# schematic1.net
KiCad netlist of a schematic drawn in EAGLE
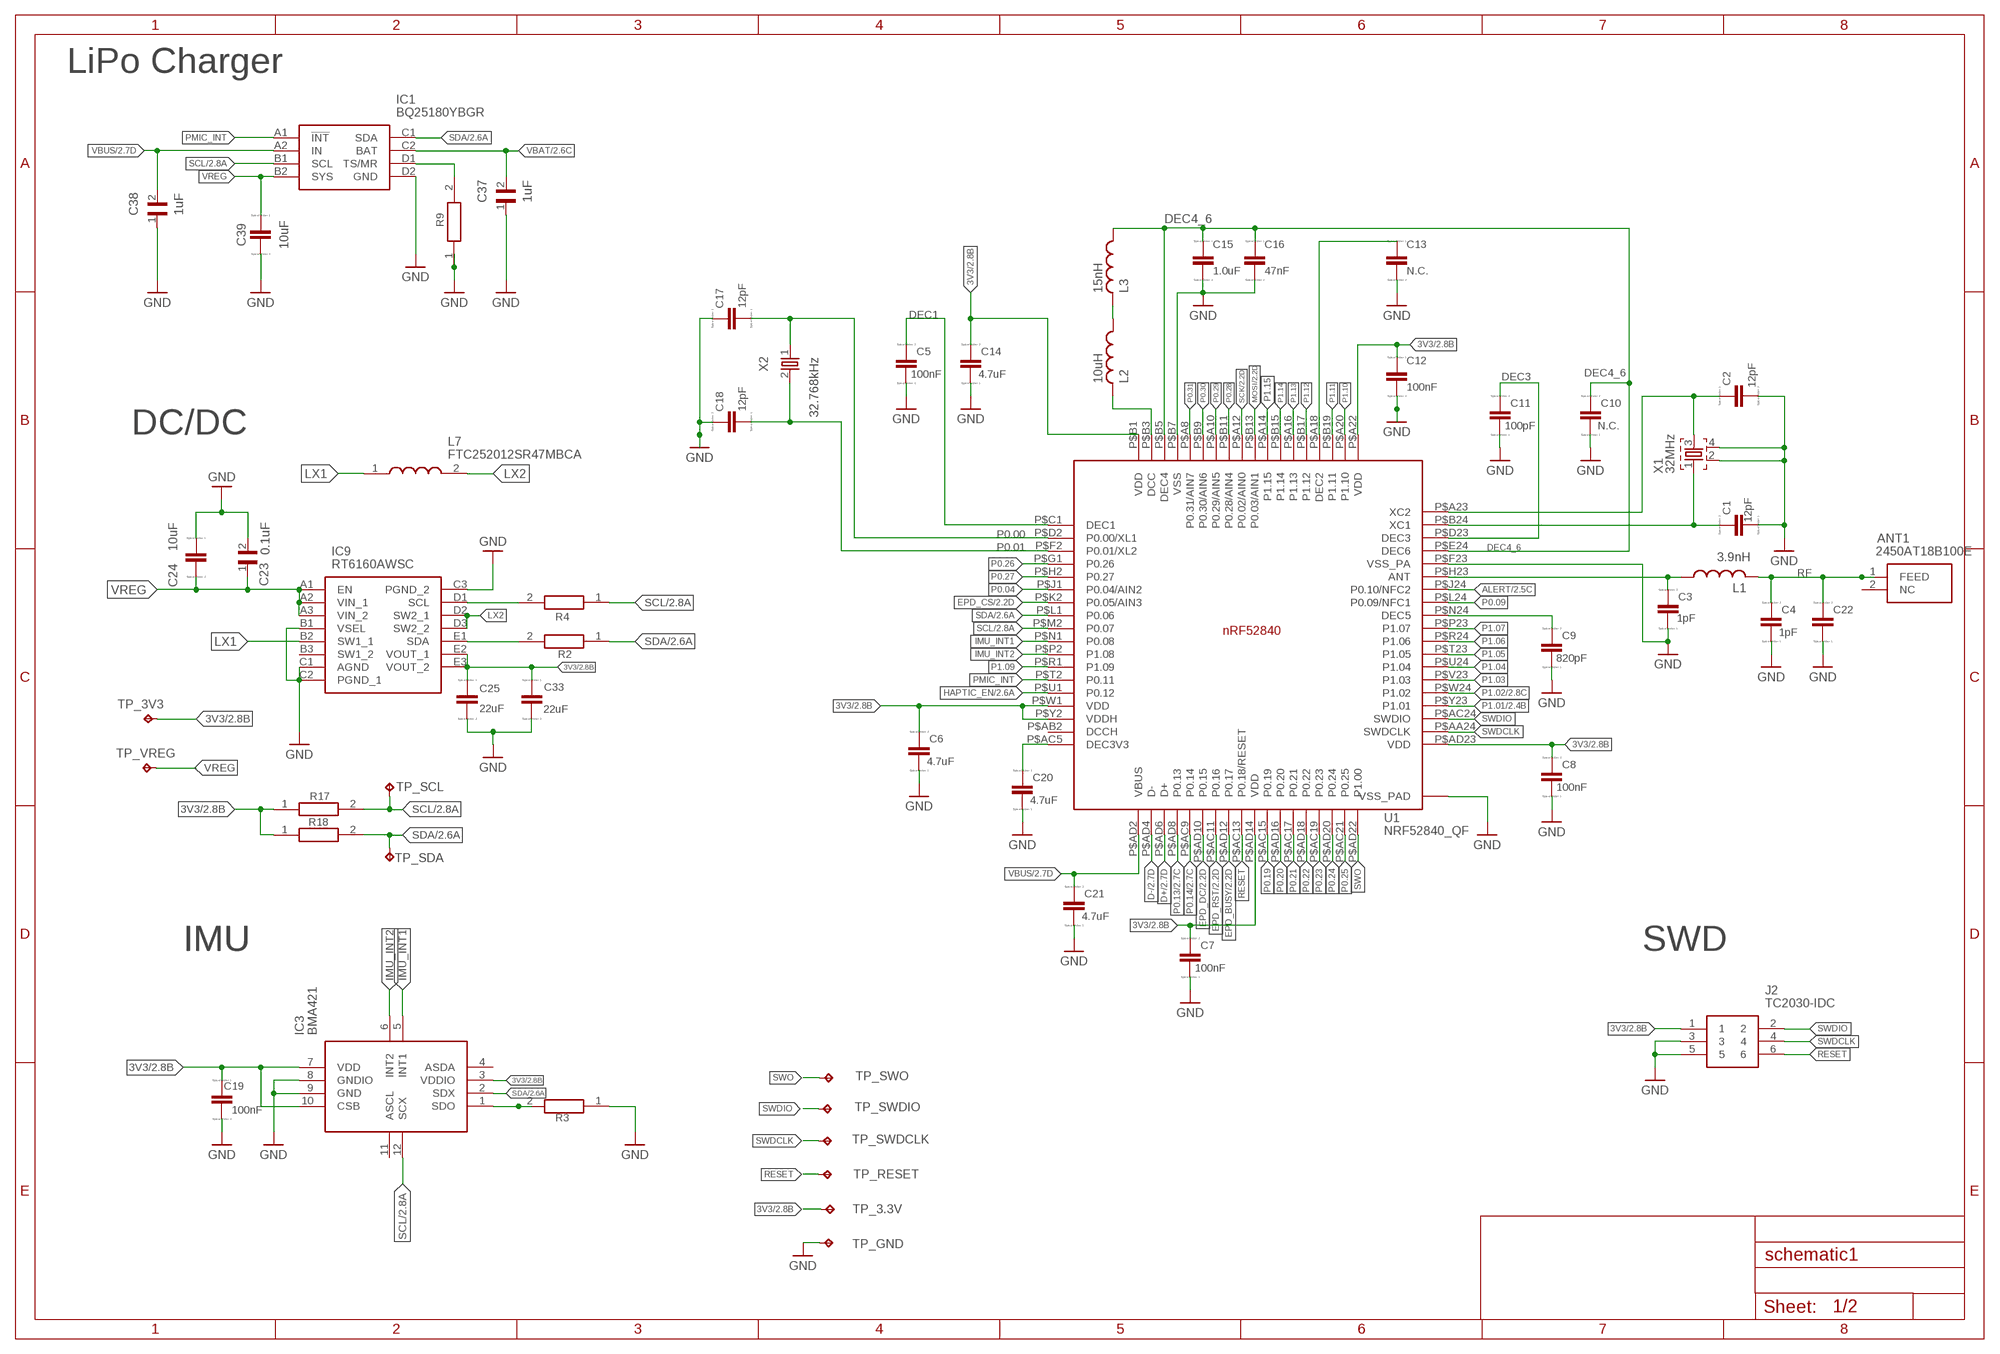
[diagram p0: schematic, sheet 1]
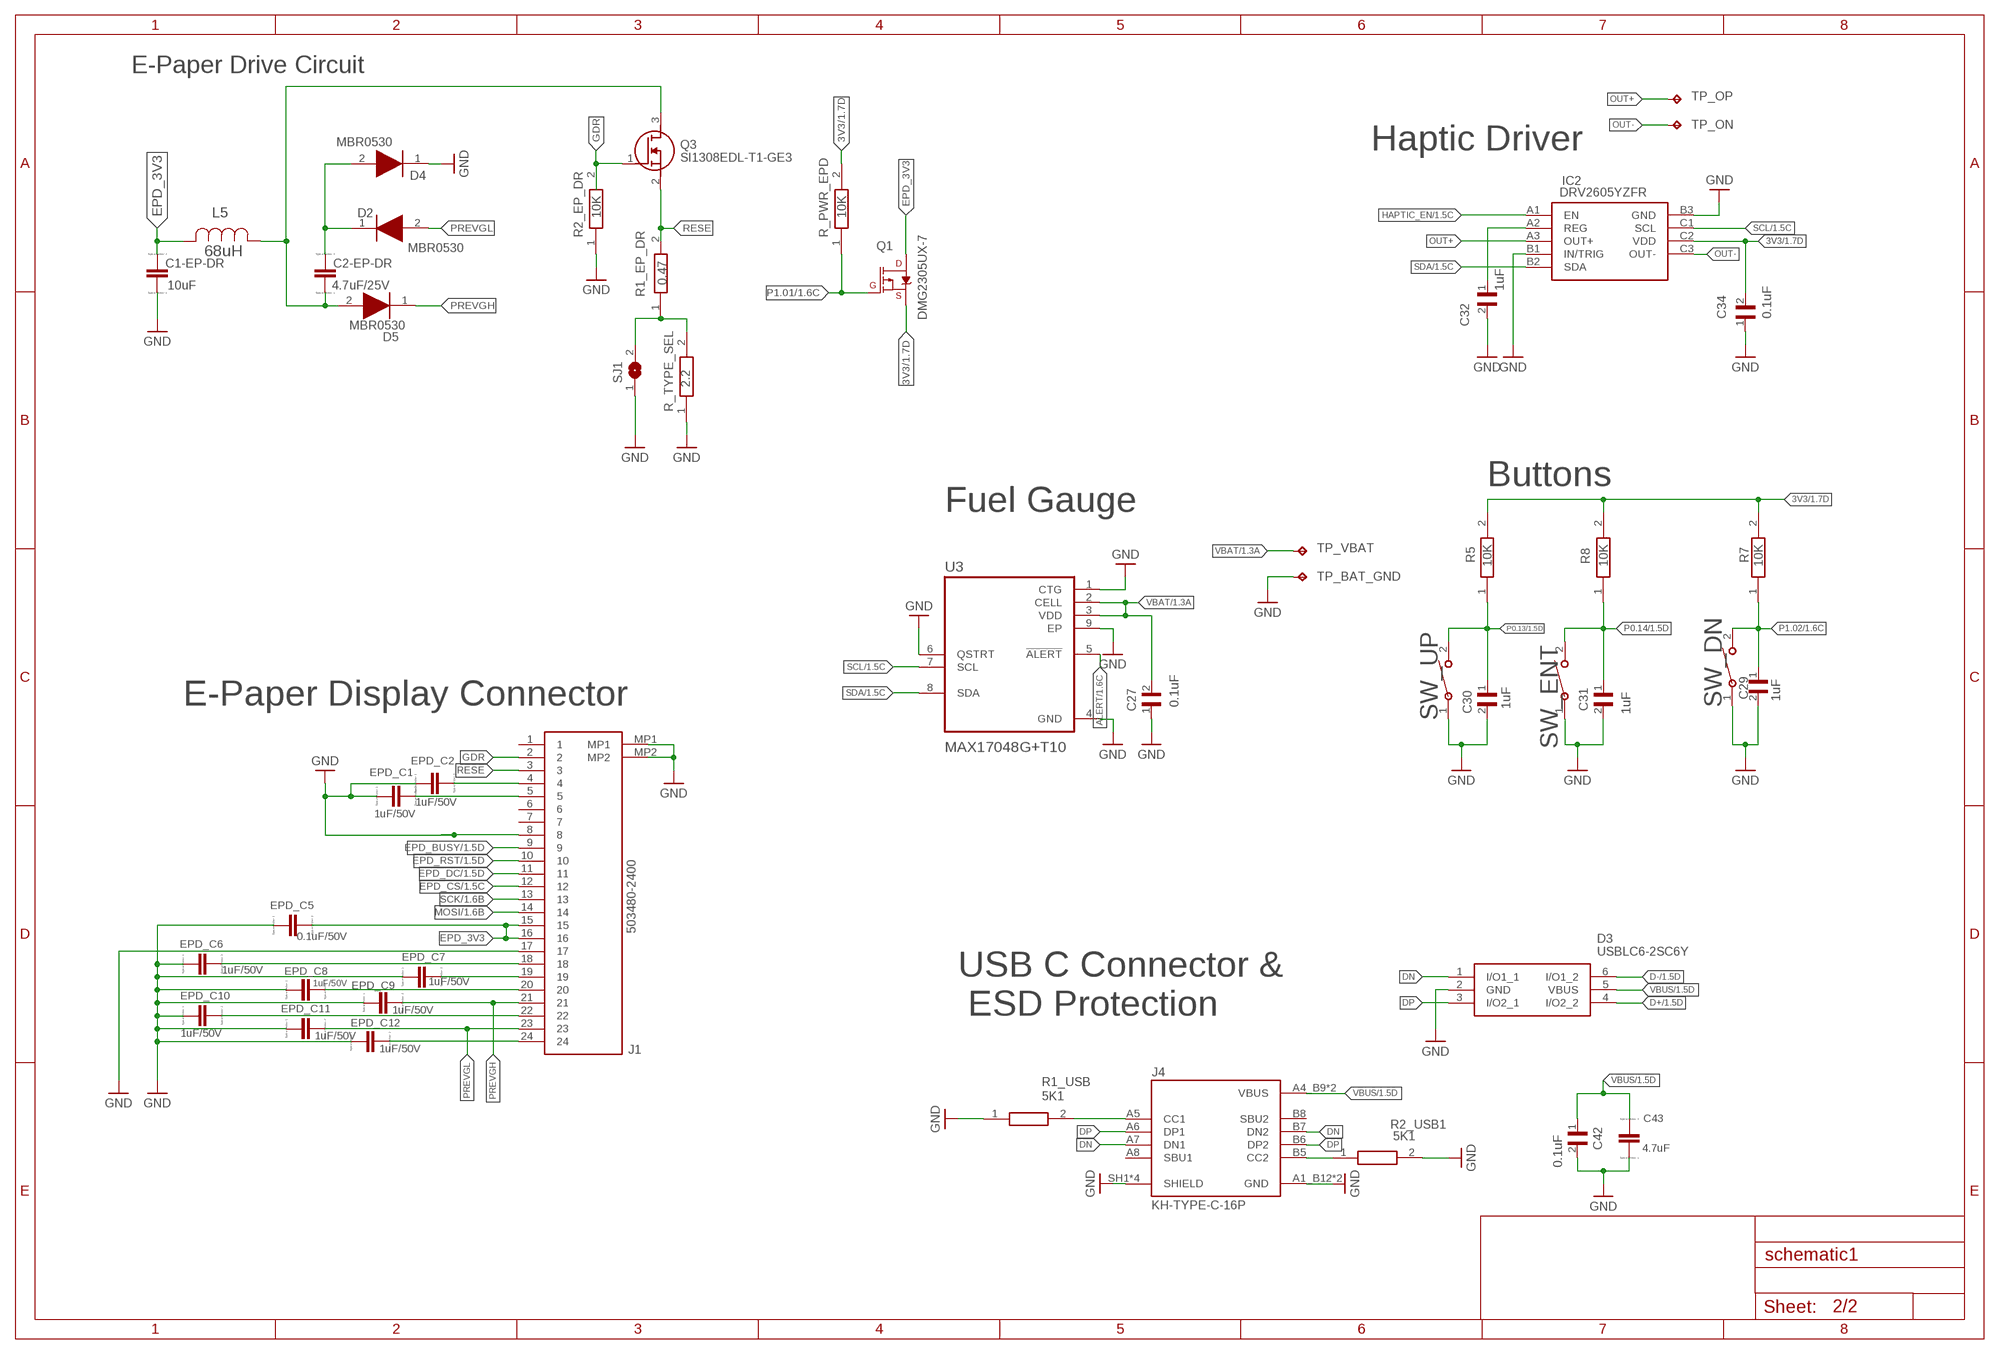
[diagram p1: schematic, sheet 2]

(export (version "E")
  (design (tool "Eeschema 10.0.6"))
  (components
    (comp (ref "ANT1")
      (value "2450AT18B100E")
      (footprint "eagle-import:2450AT18B100E_ANTC3216X140N")
      (fields (field (name "MOUSER_PART_NUMBER") "609-2450AT18B100E"))
      (libsource (lib "eagle-import") (part "2450AT18B100E_2450AT18B100E"))
    )
    (comp (ref "C1")
      (value "12pF")
      (footprint "eagle-import:ESP32_C6_LIBRARY_1_ESP32_WROVER_EAGLE-LTSPICE_C0402")
      (libsource (lib "eagle-import") (part "ESP32_C6_LIBRARY_1_ESP32_WROVER_EAGLE-LTSPICE_CC0402"))
    )
    (comp (ref "C2")
      (value "12pF")
      (footprint "eagle-import:ESP32_C6_LIBRARY_1_ESP32_WROVER_EAGLE-LTSPICE_C0402")
      (libsource (lib "eagle-import") (part "ESP32_C6_LIBRARY_1_ESP32_WROVER_EAGLE-LTSPICE_CC0402"))
    )
    (comp (ref "C3")
      (value "1pF")
      (footprint "eagle-import:ESP32_C6_LIBRARY_1_ESP32_WROVER_EAGLE-LTSPICE_C0402")
      (libsource (lib "eagle-import") (part "ESP32_C6_LIBRARY_1_ESP32_WROVER_EAGLE-LTSPICE_CC0402"))
    )
    (comp (ref "C4")
      (value "1pF")
      (footprint "eagle-import:ESP32_C6_LIBRARY_1_ESP32_WROVER_EAGLE-LTSPICE_C0402")
      (libsource (lib "eagle-import") (part "ESP32_C6_LIBRARY_1_ESP32_WROVER_EAGLE-LTSPICE_CC0402"))
    )
    (comp (ref "C5")
      (value "100nF")
      (footprint "eagle-import:ESP32_C6_LIBRARY_1_ESP32_WROVER_EAGLE-LTSPICE_C0402")
      (libsource (lib "eagle-import") (part "ESP32_C6_LIBRARY_1_ESP32_WROVER_EAGLE-LTSPICE_CC0402"))
    )
    (comp (ref "C6")
      (value "4.7uF")
      (footprint "eagle-import:ESP32_C6_LIBRARY_1_ESP32_WROVER_EAGLE-LTSPICE_C0402")
      (libsource (lib "eagle-import") (part "ESP32_C6_LIBRARY_1_ESP32_WROVER_EAGLE-LTSPICE_CC0402"))
    )
    (comp (ref "C7")
      (value "100nF")
      (footprint "eagle-import:ESP32_C6_LIBRARY_1_ESP32_WROVER_EAGLE-LTSPICE_C0402")
      (libsource (lib "eagle-import") (part "ESP32_C6_LIBRARY_1_ESP32_WROVER_EAGLE-LTSPICE_CC0402"))
    )
    (comp (ref "C8")
      (value "100nF")
      (footprint "eagle-import:ESP32_C6_LIBRARY_1_ESP32_WROVER_EAGLE-LTSPICE_C0402")
      (libsource (lib "eagle-import") (part "ESP32_C6_LIBRARY_1_ESP32_WROVER_EAGLE-LTSPICE_CC0402"))
    )
    (comp (ref "C9")
      (value "820pF")
      (footprint "eagle-import:ESP32_C6_LIBRARY_1_ESP32_WROVER_EAGLE-LTSPICE_C0402")
      (libsource (lib "eagle-import") (part "ESP32_C6_LIBRARY_1_ESP32_WROVER_EAGLE-LTSPICE_CC0402"))
    )
    (comp (ref "C10")
      (value "N.C.")
      (footprint "eagle-import:ESP32_C6_LIBRARY_1_ESP32_WROVER_EAGLE-LTSPICE_C0402")
      (libsource (lib "eagle-import") (part "ESP32_C6_LIBRARY_1_ESP32_WROVER_EAGLE-LTSPICE_CC0402"))
    )
    (comp (ref "C11")
      (value "100pF")
      (footprint "eagle-import:ESP32_C6_LIBRARY_1_ESP32_WROVER_EAGLE-LTSPICE_C0402")
      (libsource (lib "eagle-import") (part "ESP32_C6_LIBRARY_1_ESP32_WROVER_EAGLE-LTSPICE_CC0402"))
    )
    (comp (ref "C12")
      (value "100nF")
      (footprint "eagle-import:ESP32_C6_LIBRARY_1_ESP32_WROVER_EAGLE-LTSPICE_C0402")
      (libsource (lib "eagle-import") (part "ESP32_C6_LIBRARY_1_ESP32_WROVER_EAGLE-LTSPICE_CC0402"))
    )
    (comp (ref "C13")
      (value "N.C.")
      (footprint "eagle-import:ESP32_C6_LIBRARY_1_ESP32_WROVER_EAGLE-LTSPICE_C0402")
      (libsource (lib "eagle-import") (part "ESP32_C6_LIBRARY_1_ESP32_WROVER_EAGLE-LTSPICE_CC0402"))
    )
    (comp (ref "C14")
      (value "4.7uF")
      (footprint "eagle-import:ESP32_C6_LIBRARY_1_ESP32_WROVER_EAGLE-LTSPICE_C0402")
      (libsource (lib "eagle-import") (part "ESP32_C6_LIBRARY_1_ESP32_WROVER_EAGLE-LTSPICE_CC0402"))
    )
    (comp (ref "C15")
      (value "1.0uF")
      (footprint "eagle-import:ESP32_C6_LIBRARY_1_ESP32_WROVER_EAGLE-LTSPICE_C0402")
      (libsource (lib "eagle-import") (part "ESP32_C6_LIBRARY_1_ESP32_WROVER_EAGLE-LTSPICE_CC0402"))
    )
    (comp (ref "C16")
      (value "47nF")
      (footprint "eagle-import:ESP32_C6_LIBRARY_1_ESP32_WROVER_EAGLE-LTSPICE_C0402")
      (libsource (lib "eagle-import") (part "ESP32_C6_LIBRARY_1_ESP32_WROVER_EAGLE-LTSPICE_CC0402"))
    )
    (comp (ref "C17")
      (value "12pF")
      (footprint "eagle-import:ESP32_C6_LIBRARY_1_ESP32_WROVER_EAGLE-LTSPICE_C0402")
      (libsource (lib "eagle-import") (part "ESP32_C6_LIBRARY_1_ESP32_WROVER_EAGLE-LTSPICE_CC0402"))
    )
    (comp (ref "C18")
      (value "12pF")
      (footprint "eagle-import:ESP32_C6_LIBRARY_1_ESP32_WROVER_EAGLE-LTSPICE_C0402")
      (libsource (lib "eagle-import") (part "ESP32_C6_LIBRARY_1_ESP32_WROVER_EAGLE-LTSPICE_CC0402"))
    )
    (comp (ref "C19")
      (value "100nF")
      (footprint "eagle-import:ESP32_C6_LIBRARY_1_ESP32_WROVER_EAGLE-LTSPICE_C0402")
      (libsource (lib "eagle-import") (part "ESP32_C6_LIBRARY_1_ESP32_WROVER_EAGLE-LTSPICE_CC0402"))
    )
    (comp (ref "C20")
      (value "4.7uF")
      (footprint "eagle-import:ESP32_C6_LIBRARY_1_ESP32_WROVER_EAGLE-LTSPICE_C0402")
      (libsource (lib "eagle-import") (part "ESP32_C6_LIBRARY_1_ESP32_WROVER_EAGLE-LTSPICE_CC0402"))
    )
    (comp (ref "C21")
      (value "4.7uF")
      (footprint "eagle-import:ESP32_C6_LIBRARY_1_ESP32_WROVER_EAGLE-LTSPICE_C0402")
      (libsource (lib "eagle-import") (part "ESP32_C6_LIBRARY_1_ESP32_WROVER_EAGLE-LTSPICE_CC0402"))
    )
    (comp (ref "C22")
      (value "N.C.")
      (footprint "eagle-import:ESP32_C6_LIBRARY_1_ESP32_WROVER_EAGLE-LTSPICE_C0402")
      (libsource (lib "eagle-import") (part "ESP32_C6_LIBRARY_1_ESP32_WROVER_EAGLE-LTSPICE_CC0402"))
    )
    (comp (ref "C23")
      (value "0.1uF")
      (footprint "eagle-import:GRM011R60J152KE01L_2_CAPC0201X13N")
      (fields (field (name "MF") "Murata") (field (name "MP") "GRM011R60J152KE01L"))
      (libsource (lib "eagle-import") (part "GRM011R60J152KE01L_2_GRM011R60J152KE01L"))
    )
    (comp (ref "C24")
      (value "10uF")
      (footprint "eagle-import:ESP32_C6_LIBRARY_1_ESP32_WROVER_EAGLE-LTSPICE_C0402")
      (libsource (lib "eagle-import") (part "ESP32_C6_LIBRARY_1_ESP32_WROVER_EAGLE-LTSPICE_CC0402"))
    )
    (comp (ref "C25")
      (value "22uF")
      (footprint "eagle-import:ESP32_C6_LIBRARY_1_ESP32_WROVER_EAGLE-LTSPICE_C0402")
      (libsource (lib "eagle-import") (part "ESP32_C6_LIBRARY_1_ESP32_WROVER_EAGLE-LTSPICE_CC0402"))
    )
    (comp (ref "C33")
      (value "22uF")
      (footprint "eagle-import:ESP32_C6_LIBRARY_1_ESP32_WROVER_EAGLE-LTSPICE_C0402")
      (libsource (lib "eagle-import") (part "ESP32_C6_LIBRARY_1_ESP32_WROVER_EAGLE-LTSPICE_CC0402"))
    )
    (comp (ref "C37")
      (value "1uF")
      (footprint "eagle-import:GRM011R60J152KE01L_2_CAPC0201X13N")
      (fields (field (name "MF") "Murata") (field (name "MP") "GRM011R60J152KE01L"))
      (libsource (lib "eagle-import") (part "GRM011R60J152KE01L_2_GRM011R60J152KE01L"))
    )
    (comp (ref "C38")
      (value "1uF")
      (footprint "eagle-import:GRM011R60J152KE01L_2_CAPC0201X13N")
      (fields (field (name "MF") "Murata") (field (name "MP") "GRM011R60J152KE01L"))
      (libsource (lib "eagle-import") (part "GRM011R60J152KE01L_2_GRM011R60J152KE01L"))
    )
    (comp (ref "C39")
      (value "10uF")
      (footprint "eagle-import:ESP32_C6_LIBRARY_1_ESP32_WROVER_EAGLE-LTSPICE_C0402")
      (libsource (lib "eagle-import") (part "ESP32_C6_LIBRARY_1_ESP32_WROVER_EAGLE-LTSPICE_CC0402"))
    )
    (comp (ref "IC1")
      (value "BQ25180YBGR")
      (footprint "eagle-import:BQ25180YBGR_BGA8C40P2X4_100X155X50")
      (fields (field (name "MOUSER_PART_NUMBER") "595-BQ25180YBGR"))
      (libsource (lib "eagle-import") (part "BQ25180YBGR_BQ25180YBGR"))
    )
    (comp (ref "IC3")
      (value "BMA421")
      (footprint "eagle-import:BMA423_BMA423")
      (fields (field (name "ARROW_PART_NUMBER") "BMA423") (field (name "MOUSER_PART_NUMBER") "262-BMA423"))
      (libsource (lib "eagle-import") (part "BMA423_BMA423"))
    )
    (comp (ref "IC9")
      (value "RT6160AWSC")
      (footprint "eagle-import:RT6160AWSC_BGA15C40P3X5_140X230X60")
      (fields (field (name "MOUSER_PART_NUMBER") "835-RT6160AWSC"))
      (libsource (lib "eagle-import") (part "RT6160AWSC_RT6160AWSC"))
    )
    (comp (ref "J2")
      (value "TC2030-IDC")
      (footprint "eagle-import:TC2030-IDC_TC2030IDC")
      (libsource (lib "eagle-import") (part "TC2030-IDC_TC2030-IDC"))
    )
    (comp (ref "L1")
      (value "3.9nH")
      (footprint "eagle-import:NORDIC_NRF_2_RESC0402_L")
      (libsource (lib "eagle-import") (part "NORDIC_NRF_2_INDUCTOR_0402_L"))
    )
    (comp (ref "L2")
      (value "10uH")
      (footprint "eagle-import:NORDIC_NRF_2_RESC0402_L")
      (libsource (lib "eagle-import") (part "NORDIC_NRF_2_INDUCTOR_0402_L"))
    )
    (comp (ref "L3")
      (value "15nH")
      (footprint "eagle-import:NORDIC_NRF_2_RESC0402_L")
      (libsource (lib "eagle-import") (part "NORDIC_NRF_2_INDUCTOR_0402_L"))
    )
    (comp (ref "L7")
      (value "FTC252012SR47MBCA")
      (footprint "eagle-import:MLP2016SR47MT0S1_INDC2016X100N")
      (libsource (lib "eagle-import") (part "MLP2016SR47MT0S1_FTC252012SR47MBCA"))
    )
    (comp (ref "R2")
      (value "0")
      (footprint "eagle-import:ERA-1AEB3401C_0201")
      (libsource (lib "eagle-import") (part "ERA-1AEB3401C_CPF0201D7K68C1"))
    )
    (comp (ref "R3")
      (value "0")
      (footprint "eagle-import:ERA-1AEB3401C_0201")
      (libsource (lib "eagle-import") (part "ERA-1AEB3401C_CPF0201D7K68C1"))
    )
    (comp (ref "R4")
      (value "0")
      (footprint "eagle-import:ERA-1AEB3401C_0201")
      (libsource (lib "eagle-import") (part "ERA-1AEB3401C_CPF0201D7K68C1"))
    )
    (comp (ref "R9")
      (value "10K")
      (footprint "eagle-import:ERA-1AEB3401C_0201")
      (libsource (lib "eagle-import") (part "ERA-1AEB3401C_CPF0201D7K68C1"))
    )
    (comp (ref "R17")
      (value "3K3")
      (footprint "eagle-import:ERA-1AEB3401C_0201")
      (libsource (lib "eagle-import") (part "ERA-1AEB3401C_CPF0201D7K68C1"))
    )
    (comp (ref "R18")
      (value "3K3")
      (footprint "eagle-import:ERA-1AEB3401C_0201")
      (libsource (lib "eagle-import") (part "ERA-1AEB3401C_CPF0201D7K68C1"))
    )
    (comp (ref "TP_3.3V")
      (value "HECTOR_WATCH_1_TPTP20R")
      (footprint "eagle-import:HECTOR_WATCH_1_TP20R")
      (libsource (lib "eagle-import") (part "HECTOR_WATCH_1_TPTP20R"))
    )
    (comp (ref "TP_3V3")
      (value "HECTOR_WATCH_1_TPTP20R")
      (footprint "eagle-import:HECTOR_WATCH_1_TP20R")
      (libsource (lib "eagle-import") (part "HECTOR_WATCH_1_TPTP20R"))
    )
    (comp (ref "TP_GND")
      (value "HECTOR_WATCH_1_TPTP20R")
      (footprint "eagle-import:HECTOR_WATCH_1_TP20R")
      (libsource (lib "eagle-import") (part "HECTOR_WATCH_1_TPTP20R"))
    )
    (comp (ref "TP_RESET")
      (value "HECTOR_WATCH_1_TPTP20R")
      (footprint "eagle-import:HECTOR_WATCH_1_TP20R")
      (libsource (lib "eagle-import") (part "HECTOR_WATCH_1_TPTP20R"))
    )
    (comp (ref "TP_SCL")
      (value "HECTOR_WATCH_1_TPTP20R")
      (footprint "eagle-import:HECTOR_WATCH_1_TP20R")
      (libsource (lib "eagle-import") (part "HECTOR_WATCH_1_TPTP20R"))
    )
    (comp (ref "TP_SDA")
      (value "HECTOR_WATCH_1_TPTP20R")
      (footprint "eagle-import:HECTOR_WATCH_1_TP20R")
      (libsource (lib "eagle-import") (part "HECTOR_WATCH_1_TPTP20R"))
    )
    (comp (ref "TP_SWDCLK")
      (value "HECTOR_WATCH_1_TPTP20R")
      (footprint "eagle-import:HECTOR_WATCH_1_TP20R")
      (libsource (lib "eagle-import") (part "HECTOR_WATCH_1_TPTP20R"))
    )
    (comp (ref "TP_SWDIO")
      (value "HECTOR_WATCH_1_TPTP20R")
      (footprint "eagle-import:HECTOR_WATCH_1_TP20R")
      (libsource (lib "eagle-import") (part "HECTOR_WATCH_1_TPTP20R"))
    )
    (comp (ref "TP_SWO")
      (value "HECTOR_WATCH_1_TPTP20R")
      (footprint "eagle-import:HECTOR_WATCH_1_TP20R")
      (libsource (lib "eagle-import") (part "HECTOR_WATCH_1_TPTP20R"))
    )
    (comp (ref "TP_VREG")
      (value "HECTOR_WATCH_1_TPTP20R")
      (footprint "eagle-import:HECTOR_WATCH_1_TP20R")
      (libsource (lib "eagle-import") (part "HECTOR_WATCH_1_TPTP20R"))
    )
    (comp (ref "U1")
      (value "NRF52840_QF")
      (footprint "eagle-import:NORDIC_NRF_4_AQFN50P700X700X85_HS-74N")
      (libsource (lib "eagle-import") (part "NORDIC_NRF_4_NRF52840_QF"))
    )
    (comp (ref "X1")
      (value "32MHz")
      (footprint "eagle-import:NORDIC_NRF_BT-XTAL_2016_N")
      (libsource (lib "eagle-import") (part "NORDIC_NRF_XTAL_32MHZ"))
    )
    (comp (ref "X2")
      (value "32.768kHz")
      (footprint "eagle-import:NORDIC_NRF_1_XTAL_3215_N")
      (libsource (lib "eagle-import") (part "NORDIC_NRF_1_XTAL_32KHZ"))
    )
    (comp (ref "C1-EP-DR")
      (value "10uF")
      (footprint "eagle-import:ESP32_C6_LIBRARY_1_ESP32_WROVER_EAGLE-LTSPICE_C0402")
      (libsource (lib "eagle-import") (part "ESP32_C6_LIBRARY_1_ESP32_WROVER_EAGLE-LTSPICE_CC0402"))
    )
    (comp (ref "C2-EP-DR")
      (value "4.7uF/25V")
      (footprint "eagle-import:ESP32_C6_LIBRARY_1_ESP32_WROVER_EAGLE-LTSPICE_C0402")
      (libsource (lib "eagle-import") (part "ESP32_C6_LIBRARY_1_ESP32_WROVER_EAGLE-LTSPICE_CC0402"))
    )
    (comp (ref "C27")
      (value "0.1uF")
      (footprint "eagle-import:GRM011R60J152KE01L_2_CAPC0201X13N")
      (fields (field (name "MF") "Murata") (field (name "MP") "GRM011R60J152KE01L"))
      (libsource (lib "eagle-import") (part "GRM011R60J152KE01L_2_GRM011R60J152KE01L"))
    )
    (comp (ref "C29")
      (value "1uF")
      (footprint "eagle-import:GRM011R60J152KE01L_2_CAPC0201X13N")
      (fields (field (name "MF") "Murata") (field (name "MP") "GRM011R60J152KE01L"))
      (libsource (lib "eagle-import") (part "GRM011R60J152KE01L_2_GRM011R60J152KE01L"))
    )
    (comp (ref "C30")
      (value "1uF")
      (footprint "eagle-import:GRM011R60J152KE01L_2_CAPC0201X13N")
      (fields (field (name "MF") "Murata") (field (name "MP") "GRM011R60J152KE01L"))
      (libsource (lib "eagle-import") (part "GRM011R60J152KE01L_2_GRM011R60J152KE01L"))
    )
    (comp (ref "C31")
      (value "1uF")
      (footprint "eagle-import:GRM011R60J152KE01L_2_CAPC0201X13N")
      (fields (field (name "MF") "Murata") (field (name "MP") "GRM011R60J152KE01L"))
      (libsource (lib "eagle-import") (part "GRM011R60J152KE01L_2_GRM011R60J152KE01L"))
    )
    (comp (ref "C32")
      (value "1uF")
      (footprint "eagle-import:GRM011R60J152KE01L_2_CAPC0201X13N")
      (fields (field (name "MF") "Murata") (field (name "MP") "GRM011R60J152KE01L"))
      (libsource (lib "eagle-import") (part "GRM011R60J152KE01L_2_GRM011R60J152KE01L"))
    )
    (comp (ref "C34")
      (value "0.1uF")
      (footprint "eagle-import:GRM011R60J152KE01L_2_CAPC0201X13N")
      (fields (field (name "MF") "Murata") (field (name "MP") "GRM011R60J152KE01L"))
      (libsource (lib "eagle-import") (part "GRM011R60J152KE01L_2_GRM011R60J152KE01L"))
    )
    (comp (ref "C42")
      (value "0.1uF")
      (footprint "eagle-import:GRM011R60J152KE01L_2_CAPC0201X13N")
      (fields (field (name "MF") "Murata") (field (name "MP") "GRM011R60J152KE01L"))
      (libsource (lib "eagle-import") (part "GRM011R60J152KE01L_2_GRM011R60J152KE01L"))
    )
    (comp (ref "C43")
      (value "4.7uF")
      (footprint "eagle-import:ESP32_C6_LIBRARY_1_ESP32_WROVER_EAGLE-LTSPICE_C0402")
      (libsource (lib "eagle-import") (part "ESP32_C6_LIBRARY_1_ESP32_WROVER_EAGLE-LTSPICE_CC0402"))
    )
    (comp (ref "D2")
      (value "MBR0530")
      (footprint "eagle-import:ESP32_C6_LIBRARY_5_SOD3716X135N")
      (fields (field (name "MF") "ON Semiconductor"))
      (libsource (lib "eagle-import") (part "ESP32_C6_LIBRARY_5_MBR0530"))
    )
    (comp (ref "D3")
      (value "USBLC6-2SC6Y")
      (footprint "eagle-import:ESP32_C6_LIBRARY_3_SOT95P280X145-6N")
      (fields (field (name "MF") "STMicroelectronics"))
      (libsource (lib "eagle-import") (part "ESP32_C6_LIBRARY_3_USBLC6-2SC6Y"))
    )
    (comp (ref "D4")
      (value "MBR0530")
      (footprint "eagle-import:ESP32_C6_LIBRARY_5_SOD3716X135N")
      (fields (field (name "MF") "ON Semiconductor"))
      (libsource (lib "eagle-import") (part "ESP32_C6_LIBRARY_5_MBR0530"))
    )
    (comp (ref "D5")
      (value "MBR0530")
      (footprint "eagle-import:ESP32_C6_LIBRARY_5_SOD3716X135N")
      (fields (field (name "MF") "ON Semiconductor"))
      (libsource (lib "eagle-import") (part "ESP32_C6_LIBRARY_5_MBR0530"))
    )
    (comp (ref "EPD_C1")
      (value "1uF/50V")
      (footprint "eagle-import:ESP32_C6_LIBRARY_1_ESP32_WROVER_EAGLE-LTSPICE_C0402")
      (libsource (lib "eagle-import") (part "ESP32_C6_LIBRARY_1_ESP32_WROVER_EAGLE-LTSPICE_CC0402"))
    )
    (comp (ref "EPD_C2")
      (value "1uF/50V")
      (footprint "eagle-import:ESP32_C6_LIBRARY_1_ESP32_WROVER_EAGLE-LTSPICE_C0402")
      (libsource (lib "eagle-import") (part "ESP32_C6_LIBRARY_1_ESP32_WROVER_EAGLE-LTSPICE_CC0402"))
    )
    (comp (ref "EPD_C5")
      (value "0.1uF/50V")
      (footprint "eagle-import:ESP32_C6_LIBRARY_1_ESP32_WROVER_EAGLE-LTSPICE_C0402")
      (libsource (lib "eagle-import") (part "ESP32_C6_LIBRARY_1_ESP32_WROVER_EAGLE-LTSPICE_CC0402"))
    )
    (comp (ref "EPD_C6")
      (value "1uF/50V")
      (footprint "eagle-import:ESP32_C6_LIBRARY_1_ESP32_WROVER_EAGLE-LTSPICE_C0402")
      (libsource (lib "eagle-import") (part "ESP32_C6_LIBRARY_1_ESP32_WROVER_EAGLE-LTSPICE_CC0402"))
    )
    (comp (ref "EPD_C7")
      (value "1uF/50V")
      (footprint "eagle-import:ESP32_C6_LIBRARY_1_ESP32_WROVER_EAGLE-LTSPICE_C0402")
      (libsource (lib "eagle-import") (part "ESP32_C6_LIBRARY_1_ESP32_WROVER_EAGLE-LTSPICE_CC0402"))
    )
    (comp (ref "EPD_C8")
      (value "1uF/50V")
      (footprint "eagle-import:ESP32_C6_LIBRARY_1_ESP32_WROVER_EAGLE-LTSPICE_C0402")
      (libsource (lib "eagle-import") (part "ESP32_C6_LIBRARY_1_ESP32_WROVER_EAGLE-LTSPICE_CC0402"))
    )
    (comp (ref "EPD_C9")
      (value "1uF/50V")
      (footprint "eagle-import:ESP32_C6_LIBRARY_1_ESP32_WROVER_EAGLE-LTSPICE_C0402")
      (libsource (lib "eagle-import") (part "ESP32_C6_LIBRARY_1_ESP32_WROVER_EAGLE-LTSPICE_CC0402"))
    )
    (comp (ref "EPD_C10")
      (value "1uF/50V")
      (footprint "eagle-import:ESP32_C6_LIBRARY_1_ESP32_WROVER_EAGLE-LTSPICE_C0402")
      (libsource (lib "eagle-import") (part "ESP32_C6_LIBRARY_1_ESP32_WROVER_EAGLE-LTSPICE_CC0402"))
    )
    (comp (ref "EPD_C11")
      (value "1uF/50V")
      (footprint "eagle-import:ESP32_C6_LIBRARY_1_ESP32_WROVER_EAGLE-LTSPICE_C0402")
      (libsource (lib "eagle-import") (part "ESP32_C6_LIBRARY_1_ESP32_WROVER_EAGLE-LTSPICE_CC0402"))
    )
    (comp (ref "EPD_C12")
      (value "1uF/50V")
      (footprint "eagle-import:ESP32_C6_LIBRARY_1_ESP32_WROVER_EAGLE-LTSPICE_C0402")
      (libsource (lib "eagle-import") (part "ESP32_C6_LIBRARY_1_ESP32_WROVER_EAGLE-LTSPICE_CC0402"))
    )
    (comp (ref "IC2")
      (value "DRV2605YZFR")
      (footprint "eagle-import:DRV2605YZFR_BGA9C50P3X3_144X144X62")
      (libsource (lib "eagle-import") (part "DRV2605YZFR_DRV2605YZFR"))
    )
    (comp (ref "J1")
      (value "503480-2400")
      (footprint "eagle-import:503480-2400_5034802400")
      (fields (field (name "MOUSER_PART_NUMBER") "538-503480-2400"))
      (libsource (lib "eagle-import") (part "503480-2400_503480-2400"))
    )
    (comp (ref "J4")
      (value "KH-TYPE-C-16P")
      (footprint "eagle-import:KH-TYPE-C-16P_KINGHELM_KH-TYPE-C-16P")
      (fields (field (name "MF") "kinghelm"))
      (libsource (lib "eagle-import") (part "KH-TYPE-C-16P_KH-TYPE-C-16P"))
    )
    (comp (ref "L5")
      (value "68uH")
      (footprint "eagle-import:ESP32_C6_LIBRARY_2_IND_4828-WE-TPC_WRE")
      (fields
        (field (name "MANUFACTURER_PART_NUMBER") "744043680")
        (field (name "COPYRIGHT") "Copyright (C) 2024 Ultra Librarian. All rights reserved.")
      )
      (libsource (lib "eagle-import") (part "ESP32_C6_LIBRARY_2_744043680IND_4828-WE-TPC_WRE"))
    )
    (comp (ref "Q1")
      (value "DMG2305UX-7")
      (footprint "eagle-import:ESP32_C6_LIBRARY_4_ESP32_C6_LIBRARY_4_ESP32_C6_LIBRARY_4_ESP32_C6_LIBRARY_4_ESP32_WROVER_SPARKFUN-DISCRETESEMI_SOT23-3")
      (libsource (lib "eagle-import") (part "ESP32_C6_LIBRARY_4_ESP32_WROVER_SPARKFUN-DISCRETESEMI_MOSFET_PCH-DMG2305UX-7"))
    )
    (comp (ref "Q3")
      (value "SI1308EDL-T1-GE3")
      (footprint "eagle-import:ESP32_C6_LIBRARY_6_SOT65P210X110-3N")
      (fields (field (name "MF") "Vishay Siliconix"))
      (libsource (lib "eagle-import") (part "ESP32_C6_LIBRARY_6_SI1308EDL-T1-GE3"))
    )
    (comp (ref "R1_EP_DR")
      (value "0.47")
      (footprint "eagle-import:ERA-1AEB3401C_0201")
      (libsource (lib "eagle-import") (part "ERA-1AEB3401C_CPF0201D7K68C1"))
    )
    (comp (ref "R1_USB")
      (value "5K1")
      (footprint "eagle-import:ERA-1AEB3401C_0201")
      (libsource (lib "eagle-import") (part "ERA-1AEB3401C_CPF0201D7K68C1"))
    )
    (comp (ref "R2_EP_DR")
      (value "10K")
      (footprint "eagle-import:ERA-1AEB3401C_0201")
      (libsource (lib "eagle-import") (part "ERA-1AEB3401C_CPF0201D7K68C1"))
    )
    (comp (ref "R2_USB1")
      (value "5K1")
      (footprint "eagle-import:ERA-1AEB3401C_0201")
      (libsource (lib "eagle-import") (part "ERA-1AEB3401C_CPF0201D7K68C1"))
    )
    (comp (ref "R5")
      (value "10K")
      (footprint "eagle-import:ERA-1AEB3401C_0201")
      (libsource (lib "eagle-import") (part "ERA-1AEB3401C_CPF0201D7K68C1"))
    )
    (comp (ref "R7")
      (value "10K")
      (footprint "eagle-import:ERA-1AEB3401C_0201")
      (libsource (lib "eagle-import") (part "ERA-1AEB3401C_CPF0201D7K68C1"))
    )
    (comp (ref "R8")
      (value "10K")
      (footprint "eagle-import:ERA-1AEB3401C_0201")
      (libsource (lib "eagle-import") (part "ERA-1AEB3401C_CPF0201D7K68C1"))
    )
    (comp (ref "R_PWR_EPD")
      (value "10K")
      (footprint "eagle-import:ERA-1AEB3401C_0201")
      (libsource (lib "eagle-import") (part "ERA-1AEB3401C_CPF0201D7K68C1"))
    )
    (comp (ref "R_TYPE_SEL")
      (value "2.2")
      (footprint "eagle-import:ERA-1AEB3401C_0201")
      (libsource (lib "eagle-import") (part "ERA-1AEB3401C_CPF0201D7K68C1"))
    )
    (comp (ref "SJ1")
      (value "ESP32_C6_LIBRARY_7_JUMPER_SJ")
      (footprint "eagle-import:ESP32_C6_LIBRARY_7_JUMPER_SJ")
      (libsource (lib "eagle-import") (part "ESP32_C6_LIBRARY_7_JUMPER_SJ"))
    )
    (comp (ref "SW_DN")
      (value "2025-10-22_07-23-44_LIBRARY_EVP-AKE31ASW_EVP-AKE31A_PAN")
      (footprint "eagle-import:2025-10-22_07-23-44_LIBRARY_SW_EVP-AKE31A_PAN")
      (fields
        (field (name "MANUFACTURER_PART_NUMBER") "EVP-AKE31A")
        (field (name "COPYRIGHT") "Copyright (C) 2025 Ultra Librarian. All rights reserved.")
      )
      (libsource (lib "eagle-import") (part "2025-10-22_07-23-44_LIBRARY_EVP-AKE31ASW_EVP-AKE31A_PAN"))
    )
    (comp (ref "SW_ENT")
      (value "2025-10-22_07-23-44_LIBRARY_EVP-AKE31ASW_EVP-AKE31A_PAN")
      (footprint "eagle-import:2025-10-22_07-23-44_LIBRARY_SW_EVP-AKE31A_PAN")
      (fields
        (field (name "MANUFACTURER_PART_NUMBER") "EVP-AKE31A")
        (field (name "COPYRIGHT") "Copyright (C) 2025 Ultra Librarian. All rights reserved.")
      )
      (libsource (lib "eagle-import") (part "2025-10-22_07-23-44_LIBRARY_EVP-AKE31ASW_EVP-AKE31A_PAN"))
    )
    (comp (ref "SW_UP")
      (value "2025-10-22_07-23-44_LIBRARY_EVP-AKE31ASW_EVP-AKE31A_PAN")
      (footprint "eagle-import:2025-10-22_07-23-44_LIBRARY_SW_EVP-AKE31A_PAN")
      (fields
        (field (name "MANUFACTURER_PART_NUMBER") "EVP-AKE31A")
        (field (name "COPYRIGHT") "Copyright (C) 2025 Ultra Librarian. All rights reserved.")
      )
      (libsource (lib "eagle-import") (part "2025-10-22_07-23-44_LIBRARY_EVP-AKE31ASW_EVP-AKE31A_PAN"))
    )
    (comp (ref "TP_BAT_GND")
      (value "HECTOR_WATCH_1_TPTP20R")
      (footprint "eagle-import:HECTOR_WATCH_1_TP20R")
      (libsource (lib "eagle-import") (part "HECTOR_WATCH_1_TPTP20R"))
    )
    (comp (ref "TP_ON")
      (value "HECTOR_WATCH_1_TPTP20R")
      (footprint "eagle-import:HECTOR_WATCH_1_TP20R")
      (libsource (lib "eagle-import") (part "HECTOR_WATCH_1_TPTP20R"))
    )
    (comp (ref "TP_OP")
      (value "HECTOR_WATCH_1_TPTP20R")
      (footprint "eagle-import:HECTOR_WATCH_1_TP20R")
      (libsource (lib "eagle-import") (part "HECTOR_WATCH_1_TPTP20R"))
    )
    (comp (ref "TP_VBAT")
      (value "HECTOR_WATCH_1_TPTP20R")
      (footprint "eagle-import:HECTOR_WATCH_1_TP20R")
      (libsource (lib "eagle-import") (part "HECTOR_WATCH_1_TPTP20R"))
    )
    (comp (ref "U3")
      (value "MAX17048G+T10")
      (footprint "eagle-import:ESP32_C6_LIBRARY_SON50P200X200X80-9N")
      (fields (field (name "MF") "Analog Devices"))
      (libsource (lib "eagle-import") (part "ESP32_C6_LIBRARY_MAX17048G+T10"))
    )
  )
  (nets
    (net (code "1") (name "3V3") (class "Default")
      (node (ref "C12") (pin "1") (pinfunction "1_1") (pintype "passive"))
      (node (ref "C14") (pin "2") (pinfunction "2_2") (pintype "passive"))
      (node (ref "C19") (pin "1") (pinfunction "1_1") (pintype "passive"))
      (node (ref "C25") (pin "1") (pinfunction "1_1") (pintype "passive"))
      (node (ref "C33") (pin "1") (pinfunction "1_1") (pintype "passive"))
      (node (ref "C34") (pin "2") (pinfunction "2_2") (pintype "passive"))
      (node (ref "C6") (pin "2") (pinfunction "2_2") (pintype "passive"))
      (node (ref "C7") (pin "2") (pinfunction "2_2") (pintype "passive"))
      (node (ref "C8") (pin "2") (pinfunction "2_2") (pintype "passive"))
      (node (ref "IC2") (pin "C2") (pinfunction "VDD_C2") (pintype "bidirectional"))
      (node (ref "IC3") (pin "10") (pinfunction "CSB_10") (pintype "bidirectional"))
      (node (ref "IC3") (pin "3") (pinfunction "VDDIO_3") (pintype "bidirectional"))
      (node (ref "IC3") (pin "7") (pinfunction "VDD_7") (pintype "bidirectional"))
      (node (ref "IC9") (pin "E2") (pinfunction "VOUT_1_E2") (pintype "bidirectional"))
      (node (ref "IC9") (pin "E3") (pinfunction "VOUT_2_E3") (pintype "bidirectional"))
      (node (ref "J2") (pin "1") (pinfunction "1_1") (pintype "bidirectional"))
      (node (ref "Q1") (pin "2") (pinfunction "S_2") (pintype "bidirectional"))
      (node (ref "R17") (pin "1") (pinfunction "1_1") (pintype "bidirectional"))
      (node (ref "R18") (pin "1") (pinfunction "1_1") (pintype "bidirectional"))
      (node (ref "R5") (pin "2") (pinfunction "2_2") (pintype "bidirectional"))
      (node (ref "R7") (pin "2") (pinfunction "2_2") (pintype "bidirectional"))
      (node (ref "R8") (pin "2") (pinfunction "2_2") (pintype "bidirectional"))
      (node (ref "R_PWR_EPD") (pin "2") (pinfunction "2_2") (pintype "bidirectional"))
      (node (ref "TP_3.3V") (pin "TP") (pinfunction "TP_TP") (pintype "input"))
      (node (ref "TP_3V3") (pin "TP") (pinfunction "TP_TP") (pintype "input"))
      (node (ref "U1") (pin "P$A22") (pinfunction "VDD_P$A22") (pintype "power_in"))
      (node (ref "U1") (pin "P$AD14") (pinfunction "VDD_P$AD14") (pintype "power_in"))
      (node (ref "U1") (pin "P$AD23") (pinfunction "VDD_P$AD23") (pintype "power_in"))
      (node (ref "U1") (pin "P$B1") (pinfunction "VDD_P$B1") (pintype "power_in"))
      (node (ref "U1") (pin "P$W1") (pinfunction "VDD_P$W1") (pintype "power_in"))
      (node (ref "U1") (pin "P$Y2") (pinfunction "VDDH_P$Y2") (pintype "power_in"))
    )
    (net (code "2") (name "ALERT") (class "Default")
      (node (ref "U1") (pin "P$J24") (pinfunction "P0.10/NFC2_P$J24") (pintype "bidirectional"))
      (node (ref "U3") (pin "5") (pinfunction "~{ALERT}_5") (pintype "output"))
    )
    (net (code "3") (name "D+") (class "Default")
      (node (ref "D3") (pin "4") (pinfunction "I/O2_2_4") (pintype "bidirectional"))
      (node (ref "U1") (pin "P$AD6") (pinfunction "D+_P$AD6") (pintype "bidirectional"))
    )
    (net (code "4") (name "D-") (class "Default")
      (node (ref "D3") (pin "6") (pinfunction "I/O1_2_6") (pintype "bidirectional"))
      (node (ref "U1") (pin "P$AD4") (pinfunction "D-_P$AD4") (pintype "bidirectional"))
    )
    (net (code "5") (name "DEC1") (class "Default")
      (node (ref "C5") (pin "2") (pinfunction "2_2") (pintype "passive"))
      (node (ref "U1") (pin "P$C1") (pinfunction "DEC1_P$C1") (pintype "power_in"))
    )
    (net (code "6") (name "DEC3") (class "Default")
      (node (ref "C11") (pin "2") (pinfunction "2_2") (pintype "passive"))
      (node (ref "U1") (pin "P$D23") (pinfunction "DEC3_P$D23") (pintype "bidirectional"))
    )
    (net (code "7") (name "DEC4_6") (class "Default")
      (node (ref "C10") (pin "2") (pinfunction "2_2") (pintype "passive"))
      (node (ref "C15") (pin "1") (pinfunction "1_1") (pintype "passive"))
      (node (ref "C16") (pin "1") (pinfunction "1_1") (pintype "passive"))
      (node (ref "L3") (pin "1") (pinfunction "1_1") (pintype "passive"))
      (node (ref "U1") (pin "P$B5") (pinfunction "DEC4_P$B5") (pintype "power_in"))
      (node (ref "U1") (pin "P$E24") (pinfunction "DEC6_P$E24") (pintype "bidirectional"))
    )
    (net (code "8") (name "DN") (class "Default")
      (node (ref "D3") (pin "1") (pinfunction "I/O1_1_1") (pintype "bidirectional"))
      (node (ref "J4") (pin "A7") (pinfunction "DN1_A7") (pintype "bidirectional"))
      (node (ref "J4") (pin "B7") (pinfunction "DN2_B7") (pintype "bidirectional"))
    )
    (net (code "9") (name "DP") (class "Default")
      (node (ref "D3") (pin "3") (pinfunction "I/O2_1_3") (pintype "bidirectional"))
      (node (ref "J4") (pin "A6") (pinfunction "DP1_A6") (pintype "bidirectional"))
      (node (ref "J4") (pin "B6") (pinfunction "DP2_B6") (pintype "bidirectional"))
    )
    (net (code "10") (name "EPD_3V3") (class "Default")
      (node (ref "C1-EP-DR") (pin "2") (pinfunction "2_2") (pintype "passive"))
      (node (ref "EPD_C5") (pin "2") (pinfunction "2_2") (pintype "passive"))
      (node (ref "J1") (pin "15") (pinfunction "15_15") (pintype "bidirectional"))
      (node (ref "J1") (pin "16") (pinfunction "16_16") (pintype "bidirectional"))
      (node (ref "L5") (pin "2") (pinfunction "2_2") (pintype "passive"))
      (node (ref "Q1") (pin "3") (pinfunction "D_3") (pintype "bidirectional"))
    )
    (net (code "11") (name "EPD_BUSY") (class "Default")
      (node (ref "J1") (pin "9") (pinfunction "9_9") (pintype "bidirectional"))
      (node (ref "U1") (pin "P$AD12") (pinfunction "P0.17_P$AD12") (pintype "bidirectional"))
    )
    (net (code "12") (name "EPD_CS") (class "Default")
      (node (ref "J1") (pin "12") (pinfunction "12_12") (pintype "bidirectional"))
      (node (ref "U1") (pin "P$K2") (pinfunction "P0.05/AIN3_P$K2") (pintype "bidirectional"))
    )
    (net (code "13") (name "EPD_DC") (class "Default")
      (node (ref "J1") (pin "11") (pinfunction "11_11") (pintype "bidirectional"))
      (node (ref "U1") (pin "P$AD10") (pinfunction "P0.15_P$AD10") (pintype "bidirectional"))
    )
    (net (code "14") (name "EPD_RST") (class "Default")
      (node (ref "J1") (pin "10") (pinfunction "10_10") (pintype "bidirectional"))
      (node (ref "U1") (pin "P$AC11") (pinfunction "P0.16_P$AC11") (pintype "bidirectional"))
    )
    (net (code "15") (name "GDR") (class "Default")
      (node (ref "J1") (pin "2") (pinfunction "2_2") (pintype "bidirectional"))
      (node (ref "Q3") (pin "1") (pinfunction "G_1") (pintype "bidirectional"))
      (node (ref "R2_EP_DR") (pin "2") (pinfunction "2_2") (pintype "bidirectional"))
    )
    (net (code "16") (name "GND") (class "Default")
      (node (ref "C1") (pin "1") (pinfunction "1_1") (pintype "passive"))
      (node (ref "C1-EP-DR") (pin "1") (pinfunction "1_1") (pintype "passive"))
      (node (ref "C10") (pin "1") (pinfunction "1_1") (pintype "passive"))
      (node (ref "C11") (pin "1") (pinfunction "1_1") (pintype "passive"))
      (node (ref "C12") (pin "2") (pinfunction "2_2") (pintype "passive"))
      (node (ref "C13") (pin "2") (pinfunction "2_2") (pintype "passive"))
      (node (ref "C14") (pin "1") (pinfunction "1_1") (pintype "passive"))
      (node (ref "C15") (pin "2") (pinfunction "2_2") (pintype "passive"))
      (node (ref "C16") (pin "2") (pinfunction "2_2") (pintype "passive"))
      (node (ref "C17") (pin "2") (pinfunction "2_2") (pintype "passive"))
      (node (ref "C18") (pin "2") (pinfunction "2_2") (pintype "passive"))
      (node (ref "C19") (pin "2") (pinfunction "2_2") (pintype "passive"))
      (node (ref "C2") (pin "2") (pinfunction "2_2") (pintype "passive"))
      (node (ref "C20") (pin "1") (pinfunction "1_1") (pintype "passive"))
      (node (ref "C21") (pin "1") (pinfunction "1_1") (pintype "passive"))
      (node (ref "C22") (pin "1") (pinfunction "1_1") (pintype "passive"))
      (node (ref "C23") (pin "2") (pinfunction "2_2") (pintype "passive"))
      (node (ref "C24") (pin "1") (pinfunction "1_1") (pintype "passive"))
      (node (ref "C25") (pin "2") (pinfunction "2_2") (pintype "passive"))
      (node (ref "C27") (pin "1") (pinfunction "1_1") (pintype "passive"))
      (node (ref "C29") (pin "2") (pinfunction "2_2") (pintype "passive"))
      (node (ref "C3") (pin "1") (pinfunction "1_1") (pintype "passive"))
      (node (ref "C30") (pin "2") (pinfunction "2_2") (pintype "passive"))
      (node (ref "C31") (pin "2") (pinfunction "2_2") (pintype "passive"))
      (node (ref "C32") (pin "2") (pinfunction "2_2") (pintype "passive"))
      (node (ref "C33") (pin "2") (pinfunction "2_2") (pintype "passive"))
      (node (ref "C34") (pin "1") (pinfunction "1_1") (pintype "passive"))
      (node (ref "C37") (pin "1") (pinfunction "1_1") (pintype "passive"))
      (node (ref "C38") (pin "1") (pinfunction "1_1") (pintype "passive"))
      (node (ref "C39") (pin "2") (pinfunction "2_2") (pintype "passive"))
      (node (ref "C4") (pin "1") (pinfunction "1_1") (pintype "passive"))
      (node (ref "C42") (pin "2") (pinfunction "2_2") (pintype "passive"))
      (node (ref "C43") (pin "1") (pinfunction "1_1") (pintype "passive"))
      (node (ref "C5") (pin "1") (pinfunction "1_1") (pintype "passive"))
      (node (ref "C6") (pin "1") (pinfunction "1_1") (pintype "passive"))
      (node (ref "C7") (pin "1") (pinfunction "1_1") (pintype "passive"))
      (node (ref "C8") (pin "1") (pinfunction "1_1") (pintype "passive"))
      (node (ref "C9") (pin "1") (pinfunction "1_1") (pintype "passive"))
      (node (ref "D3") (pin "2") (pinfunction "GND_2") (pintype "bidirectional"))
      (node (ref "D4") (pin "1") (pinfunction "K_1") (pintype "bidirectional"))
      (node (ref "EPD_C1") (pin "1") (pinfunction "1_1") (pintype "passive"))
      (node (ref "EPD_C10") (pin "1") (pinfunction "1_1") (pintype "passive"))
      (node (ref "EPD_C11") (pin "1") (pinfunction "1_1") (pintype "passive"))
      (node (ref "EPD_C12") (pin "1") (pinfunction "1_1") (pintype "passive"))
      (node (ref "EPD_C2") (pin "1") (pinfunction "1_1") (pintype "passive"))
      (node (ref "EPD_C5") (pin "1") (pinfunction "1_1") (pintype "passive"))
      (node (ref "EPD_C6") (pin "1") (pinfunction "1_1") (pintype "passive"))
      (node (ref "EPD_C7") (pin "1") (pinfunction "1_1") (pintype "passive"))
      (node (ref "EPD_C8") (pin "1") (pinfunction "1_1") (pintype "passive"))
      (node (ref "EPD_C9") (pin "1") (pinfunction "1_1") (pintype "passive"))
      (node (ref "IC1") (pin "D2") (pinfunction "GND_D2") (pintype "bidirectional"))
      (node (ref "IC2") (pin "B1") (pinfunction "IN/TRIG_B1") (pintype "bidirectional"))
      (node (ref "IC2") (pin "B3") (pinfunction "GND_B3") (pintype "bidirectional"))
      (node (ref "IC3") (pin "8") (pinfunction "GNDIO_8") (pintype "bidirectional"))
      (node (ref "IC3") (pin "9") (pinfunction "GND_9") (pintype "bidirectional"))
      (node (ref "IC9") (pin "B1") (pinfunction "VSEL_B1") (pintype "bidirectional"))
      (node (ref "IC9") (pin "C1") (pinfunction "AGND_C1") (pintype "bidirectional"))
      (node (ref "IC9") (pin "C2") (pinfunction "PGND_1_C2") (pintype "bidirectional"))
      (node (ref "IC9") (pin "C3") (pinfunction "PGND_2_C3") (pintype "bidirectional"))
      (node (ref "J1") (pin "17") (pinfunction "17_17") (pintype "bidirectional"))
      (node (ref "J1") (pin "8") (pinfunction "8_8") (pintype "bidirectional"))
      (node (ref "J1") (pin "MP1") (pinfunction "MP1_MP1") (pintype "bidirectional"))
      (node (ref "J1") (pin "MP2") (pinfunction "MP2_MP2") (pintype "bidirectional"))
      (node (ref "J2") (pin "3") (pinfunction "3_3") (pintype "bidirectional"))
      (node (ref "J2") (pin "5") (pinfunction "5_5") (pintype "bidirectional"))
      (node (ref "J4") (pin "A12_B1") (pinfunction "GND_A12_B1") (pintype "power_in"))
      (node (ref "J4") (pin "A1_B12") (pinfunction "GND_A1_B12") (pintype "power_in"))
      (node (ref "J4") (pin "SH1") (pinfunction "SHIELD_SH1") (pintype "passive"))
      (node (ref "J4") (pin "SH2") (pinfunction "SHIELD_SH2") (pintype "passive"))
      (node (ref "J4") (pin "SH3") (pinfunction "SHIELD_SH3") (pintype "passive"))
      (node (ref "J4") (pin "SH4") (pinfunction "SHIELD_SH4") (pintype "passive"))
      (node (ref "R1_USB") (pin "1") (pinfunction "1_1") (pintype "bidirectional"))
      (node (ref "R2_EP_DR") (pin "1") (pinfunction "1_1") (pintype "bidirectional"))
      (node (ref "R2_USB1") (pin "2") (pinfunction "2_2") (pintype "bidirectional"))
      (node (ref "R3") (pin "1") (pinfunction "1_1") (pintype "bidirectional"))
      (node (ref "R9") (pin "1") (pinfunction "1_1") (pintype "bidirectional"))
      (node (ref "R_TYPE_SEL") (pin "1") (pinfunction "1_1") (pintype "bidirectional"))
      (node (ref "SJ1") (pin "1") (pinfunction "1_1") (pintype "passive"))
      (node (ref "SW_DN") (pin "1") (pinfunction "1_1") (pintype "passive"))
      (node (ref "SW_ENT") (pin "1") (pinfunction "1_1") (pintype "passive"))
      (node (ref "SW_UP") (pin "1") (pinfunction "1_1") (pintype "passive"))
      (node (ref "TP_BAT_GND") (pin "TP") (pinfunction "TP_TP") (pintype "input"))
      (node (ref "TP_GND") (pin "TP") (pinfunction "TP_TP") (pintype "input"))
      (node (ref "U1") (pin "P$74") (pinfunction "VSS_PAD_P$74") (pintype "bidirectional"))
      (node (ref "U1") (pin "P$75") (pinfunction "VSS_PAD_P$75") (pintype "bidirectional"))
      (node (ref "U1") (pin "P$76") (pinfunction "VSS_PAD_P$76") (pintype "bidirectional"))
      (node (ref "U1") (pin "P$77") (pinfunction "VSS_PAD_P$77") (pintype "bidirectional"))
      (node (ref "U1") (pin "P$78") (pinfunction "VSS_PAD_P$78") (pintype "bidirectional"))
      (node (ref "U1") (pin "P$79") (pinfunction "VSS_PAD_P$79") (pintype "bidirectional"))
      (node (ref "U1") (pin "P$80") (pinfunction "VSS_PAD_P$80") (pintype "bidirectional"))
      (node (ref "U1") (pin "P$81") (pinfunction "VSS_PAD_P$81") (pintype "bidirectional"))
      (node (ref "U1") (pin "P$82") (pinfunction "VSS_PAD_P$82") (pintype "bidirectional"))
      (node (ref "U1") (pin "P$83") (pinfunction "VSS_PAD_P$83") (pintype "bidirectional"))
      (node (ref "U1") (pin "P$84") (pinfunction "VSS_PAD_P$84") (pintype "bidirectional"))
      (node (ref "U1") (pin "P$85") (pinfunction "VSS_PAD_P$85") (pintype "bidirectional"))
      (node (ref "U1") (pin "P$86") (pinfunction "VSS_PAD_P$86") (pintype "bidirectional"))
      (node (ref "U1") (pin "P$87") (pinfunction "VSS_PAD_P$87") (pintype "bidirectional"))
      (node (ref "U1") (pin "P$88") (pinfunction "VSS_PAD_P$88") (pintype "bidirectional"))
      (node (ref "U1") (pin "P$89") (pinfunction "VSS_PAD_P$89") (pintype "bidirectional"))
      (node (ref "U1") (pin "P$90") (pinfunction "VSS_PAD_P$90") (pintype "bidirectional"))
      (node (ref "U1") (pin "P$B7") (pinfunction "VSS_P$B7") (pintype "power_in"))
      (node (ref "U1") (pin "P$F23") (pinfunction "VSS_PA_P$F23") (pintype "bidirectional"))
      (node (ref "U3") (pin "1") (pinfunction "CTG_1") (pintype "power_in"))
      (node (ref "U3") (pin "4") (pinfunction "GND_4") (pintype "power_in"))
      (node (ref "U3") (pin "6") (pinfunction "QSTRT_6") (pintype "input"))
      (node (ref "U3") (pin "9") (pinfunction "EP_9") (pintype "power_in"))
      (node (ref "X1") (pin "2") (pinfunction "2_2") (pintype "passive"))
      (node (ref "X1") (pin "4") (pinfunction "4_4") (pintype "passive"))
    )
    (net (code "17") (name "HAPTIC_EN") (class "Default")
      (node (ref "IC2") (pin "A1") (pinfunction "EN_A1") (pintype "bidirectional"))
      (node (ref "U1") (pin "P$U1") (pinfunction "P0.12_P$U1") (pintype "bidirectional"))
    )
    (net (code "18") (name "IMU_INT1") (class "Default")
      (node (ref "IC3") (pin "5") (pinfunction "INT1_5") (pintype "bidirectional"))
      (node (ref "U1") (pin "P$N1") (pinfunction "P0.08_P$N1") (pintype "bidirectional"))
    )
    (net (code "19") (name "IMU_INT2") (class "Default")
      (node (ref "IC3") (pin "6") (pinfunction "INT2_6") (pintype "bidirectional"))
      (node (ref "U1") (pin "P$P2") (pinfunction "P1.08_P$P2") (pintype "bidirectional"))
    )
    (net (code "20") (name "LX1") (class "Default")
      (node (ref "IC9") (pin "B2") (pinfunction "SW1_1_B2") (pintype "bidirectional"))
      (node (ref "L7") (pin "1") (pinfunction "1_1") (pintype "bidirectional"))
    )
    (net (code "21") (name "LX2") (class "Default")
      (node (ref "IC9") (pin "D2") (pinfunction "SW2_1_D2") (pintype "bidirectional"))
      (node (ref "IC9") (pin "D3") (pinfunction "SW2_2_D3") (pintype "bidirectional"))
      (node (ref "L7") (pin "2") (pinfunction "2_2") (pintype "bidirectional"))
    )
    (net (code "22") (name "MOSI") (class "Default")
      (node (ref "J1") (pin "14") (pinfunction "14_14") (pintype "bidirectional"))
      (node (ref "U1") (pin "P$B13") (pinfunction "P0.03/AIN1_P$B13") (pintype "bidirectional"))
    )
    (net (code "23") (name "Net-(D2-K)") (class "Default")
      (node (ref "C2-EP-DR") (pin "2") (pinfunction "2_2") (pintype "passive"))
      (node (ref "D2") (pin "1") (pinfunction "K_1") (pintype "bidirectional"))
      (node (ref "D4") (pin "2") (pinfunction "A_2") (pintype "bidirectional"))
    )
    (net (code "24") (name "Net-(D5-A)") (class "Default")
      (node (ref "C2-EP-DR") (pin "1") (pinfunction "1_1") (pintype "passive"))
      (node (ref "D5") (pin "2") (pinfunction "A_2") (pintype "bidirectional"))
      (node (ref "L5") (pin "1") (pinfunction "1_1") (pintype "passive"))
      (node (ref "Q3") (pin "3") (pinfunction "D_3") (pintype "bidirectional"))
    )
    (net (code "25") (name "Net-(EPD_C1-Pad2)") (class "Default")
      (node (ref "EPD_C1") (pin "2") (pinfunction "2_2") (pintype "passive"))
      (node (ref "J1") (pin "5") (pinfunction "5_5") (pintype "bidirectional"))
    )
    (net (code "26") (name "Net-(EPD_C2-Pad2)") (class "Default")
      (node (ref "EPD_C2") (pin "2") (pinfunction "2_2") (pintype "passive"))
      (node (ref "J1") (pin "4") (pinfunction "4_4") (pintype "bidirectional"))
    )
    (net (code "27") (name "Net-(EPD_C6-Pad2)") (class "Default")
      (node (ref "EPD_C6") (pin "2") (pinfunction "2_2") (pintype "passive"))
      (node (ref "J1") (pin "18") (pinfunction "18_18") (pintype "bidirectional"))
    )
    (net (code "28") (name "Net-(EPD_C7-Pad2)") (class "Default")
      (node (ref "EPD_C7") (pin "2") (pinfunction "2_2") (pintype "passive"))
      (node (ref "J1") (pin "19") (pinfunction "19_19") (pintype "bidirectional"))
    )
    (net (code "29") (name "Net-(EPD_C8-Pad2)") (class "Default")
      (node (ref "EPD_C8") (pin "2") (pinfunction "2_2") (pintype "passive"))
      (node (ref "J1") (pin "20") (pinfunction "20_20") (pintype "bidirectional"))
    )
    (net (code "30") (name "Net-(EPD_C10-Pad2)") (class "Default")
      (node (ref "EPD_C10") (pin "2") (pinfunction "2_2") (pintype "passive"))
      (node (ref "J1") (pin "22") (pinfunction "22_22") (pintype "bidirectional"))
    )
    (net (code "31") (name "Net-(EPD_C12-Pad2)") (class "Default")
      (node (ref "EPD_C12") (pin "2") (pinfunction "2_2") (pintype "passive"))
      (node (ref "J1") (pin "24") (pinfunction "24_24") (pintype "bidirectional"))
    )
    (net (code "32") (name "Net-(IC1-TS{slash}MR)") (class "Default")
      (node (ref "IC1") (pin "D1") (pinfunction "TS/MR_D1") (pintype "bidirectional"))
      (node (ref "R9") (pin "2") (pinfunction "2_2") (pintype "bidirectional"))
    )
    (net (code "33") (name "Net-(IC2-REG)") (class "Default")
      (node (ref "C32") (pin "1") (pinfunction "1_1") (pintype "passive"))
      (node (ref "IC2") (pin "A2") (pinfunction "REG_A2") (pintype "bidirectional"))
    )
    (net (code "34") (name "Net-(IC3-SDO)") (class "Default")
      (node (ref "IC3") (pin "1") (pinfunction "SDO_1") (pintype "bidirectional"))
      (node (ref "R3") (pin "2") (pinfunction "2_2") (pintype "bidirectional"))
    )
    (net (code "35") (name "Net-(IC9-SCL)") (class "Default")
      (node (ref "IC9") (pin "D1") (pinfunction "SCL_D1") (pintype "bidirectional"))
      (node (ref "R4") (pin "2") (pinfunction "2_2") (pintype "bidirectional"))
    )
    (net (code "36") (name "Net-(IC9-SDA)") (class "Default")
      (node (ref "IC9") (pin "E1") (pinfunction "SDA_E1") (pintype "bidirectional"))
      (node (ref "R2") (pin "2") (pinfunction "2_2") (pintype "bidirectional"))
    )
    (net (code "37") (name "Net-(J4-CC1)") (class "Default")
      (node (ref "J4") (pin "A5") (pinfunction "CC1_A5") (pintype "bidirectional"))
      (node (ref "R1_USB") (pin "2") (pinfunction "2_2") (pintype "bidirectional"))
    )
    (net (code "38") (name "Net-(J4-CC2)") (class "Default")
      (node (ref "J4") (pin "B5") (pinfunction "CC2_B5") (pintype "bidirectional"))
      (node (ref "R2_USB1") (pin "1") (pinfunction "1_1") (pintype "bidirectional"))
    )
    (net (code "39") (name "Net-(L2-Pad1)") (class "Default")
      (node (ref "L2") (pin "1") (pinfunction "1_1") (pintype "passive"))
      (node (ref "L3") (pin "2") (pinfunction "2_2") (pintype "passive"))
    )
    (net (code "40") (name "Net-(R1_EP_DR-Pad1)") (class "Default")
      (node (ref "R1_EP_DR") (pin "1") (pinfunction "1_1") (pintype "bidirectional"))
      (node (ref "R_TYPE_SEL") (pin "2") (pinfunction "2_2") (pintype "bidirectional"))
      (node (ref "SJ1") (pin "2") (pinfunction "2_2") (pintype "passive"))
    )
    (net (code "41") (name "Net-(U1-ANT)") (class "Default")
      (node (ref "C3") (pin "2") (pinfunction "2_2") (pintype "passive"))
      (node (ref "L1") (pin "2") (pinfunction "2_2") (pintype "passive"))
      (node (ref "U1") (pin "P$H23") (pinfunction "ANT_P$H23") (pintype "bidirectional"))
    )
    (net (code "42") (name "Net-(U1-DCC)") (class "Default")
      (node (ref "L2") (pin "2") (pinfunction "2_2") (pintype "passive"))
      (node (ref "U1") (pin "P$B3") (pinfunction "DCC_P$B3") (pintype "output"))
    )
    (net (code "43") (name "Net-(U1-DEC2)") (class "Default")
      (node (ref "C13") (pin "1") (pinfunction "1_1") (pintype "passive"))
      (node (ref "U1") (pin "P$A18") (pinfunction "DEC2_P$A18") (pintype "bidirectional"))
    )
    (net (code "44") (name "Net-(U1-DEC3V3)") (class "Default")
      (node (ref "C20") (pin "2") (pinfunction "2_2") (pintype "passive"))
      (node (ref "U1") (pin "P$AC5") (pinfunction "DEC3V3_P$AC5") (pintype "bidirectional"))
    )
    (net (code "45") (name "Net-(U1-DEC5)") (class "Default")
      (node (ref "C9") (pin "2") (pinfunction "2_2") (pintype "passive"))
      (node (ref "U1") (pin "P$N24") (pinfunction "DEC5_P$N24") (pintype "bidirectional"))
    )
    (net (code "46") (name "Net-(U1-XC1)") (class "Default")
      (node (ref "C1") (pin "2") (pinfunction "2_2") (pintype "passive"))
      (node (ref "U1") (pin "P$B24") (pinfunction "XC1_P$B24") (pintype "input"))
      (node (ref "X1") (pin "1") (pinfunction "1_1") (pintype "passive"))
    )
    (net (code "47") (name "Net-(U1-XC2)") (class "Default")
      (node (ref "C2") (pin "1") (pinfunction "1_1") (pintype "passive"))
      (node (ref "U1") (pin "P$A23") (pinfunction "XC2_P$A23") (pintype "output"))
      (node (ref "X1") (pin "3") (pinfunction "3_3") (pintype "passive"))
    )
    (net (code "48") (name "OUT+") (class "Default")
      (node (ref "IC2") (pin "A3") (pinfunction "OUT+_A3") (pintype "bidirectional"))
      (node (ref "TP_OP") (pin "TP") (pinfunction "TP_TP") (pintype "input"))
    )
    (net (code "49") (name "OUT-") (class "Default")
      (node (ref "IC2") (pin "C3") (pinfunction "OUT-_C3") (pintype "bidirectional"))
      (node (ref "TP_ON") (pin "TP") (pinfunction "TP_TP") (pintype "input"))
    )
    (net (code "50") (name "P0.00") (class "Default")
      (node (ref "C17") (pin "1") (pinfunction "1_1") (pintype "passive"))
      (node (ref "U1") (pin "P$D2") (pinfunction "P0.00/XL1_P$D2") (pintype "bidirectional"))
      (node (ref "X2") (pin "1") (pinfunction "1_1") (pintype "passive"))
    )
    (net (code "51") (name "P0.01") (class "Default")
      (node (ref "C18") (pin "1") (pinfunction "1_1") (pintype "passive"))
      (node (ref "U1") (pin "P$F2") (pinfunction "P0.01/XL2_P$F2") (pintype "bidirectional"))
      (node (ref "X2") (pin "2") (pinfunction "2_2") (pintype "passive"))
    )
    (net (code "52") (name "P0.04") (class "Default")
      (node (ref "U1") (pin "P$J1") (pinfunction "P0.04/AIN2_P$J1") (pintype "bidirectional"))
    )
    (net (code "53") (name "P0.09") (class "Default")
      (node (ref "U1") (pin "P$L24") (pinfunction "P0.09/NFC1_P$L24") (pintype "bidirectional"))
    )
    (net (code "54") (name "P0.13") (class "Default")
      (node (ref "C30") (pin "1") (pinfunction "1_1") (pintype "passive"))
      (node (ref "R5") (pin "1") (pinfunction "1_1") (pintype "bidirectional"))
      (node (ref "SW_UP") (pin "2") (pinfunction "2_2") (pintype "passive"))
      (node (ref "U1") (pin "P$AD8") (pinfunction "P0.13_P$AD8") (pintype "bidirectional"))
    )
    (net (code "55") (name "P0.14") (class "Default")
      (node (ref "C31") (pin "1") (pinfunction "1_1") (pintype "passive"))
      (node (ref "R8") (pin "1") (pinfunction "1_1") (pintype "bidirectional"))
      (node (ref "SW_ENT") (pin "2") (pinfunction "2_2") (pintype "passive"))
      (node (ref "U1") (pin "P$AC9") (pinfunction "P0.14_P$AC9") (pintype "bidirectional"))
    )
    (net (code "56") (name "P0.19") (class "Default")
      (node (ref "U1") (pin "P$AC15") (pinfunction "P0.19_P$AC15") (pintype "bidirectional"))
    )
    (net (code "57") (name "P0.20") (class "Default")
      (node (ref "U1") (pin "P$AD16") (pinfunction "P0.20_P$AD16") (pintype "bidirectional"))
    )
    (net (code "58") (name "P0.21") (class "Default")
      (node (ref "U1") (pin "P$AC17") (pinfunction "P0.21_P$AC17") (pintype "bidirectional"))
    )
    (net (code "59") (name "P0.22") (class "Default")
      (node (ref "U1") (pin "P$AD18") (pinfunction "P0.22_P$AD18") (pintype "bidirectional"))
    )
    (net (code "60") (name "P0.23") (class "Default")
      (node (ref "U1") (pin "P$AC19") (pinfunction "P0.23_P$AC19") (pintype "bidirectional"))
    )
    (net (code "61") (name "P0.24") (class "Default")
      (node (ref "U1") (pin "P$AD20") (pinfunction "P0.24_P$AD20") (pintype "bidirectional"))
    )
    (net (code "62") (name "P0.25") (class "Default")
      (node (ref "U1") (pin "P$AC21") (pinfunction "P0.25_P$AC21") (pintype "bidirectional"))
    )
    (net (code "63") (name "P0.26") (class "Default")
      (node (ref "U1") (pin "P$G1") (pinfunction "P0.26_P$G1") (pintype "bidirectional"))
    )
    (net (code "64") (name "P0.27") (class "Default")
      (node (ref "U1") (pin "P$H2") (pinfunction "P0.27_P$H2") (pintype "bidirectional"))
    )
    (net (code "65") (name "P0.28") (class "Default")
      (node (ref "U1") (pin "P$B11") (pinfunction "P0.28/AIN4_P$B11") (pintype "bidirectional"))
    )
    (net (code "66") (name "P0.29") (class "Default")
      (node (ref "U1") (pin "P$A10") (pinfunction "P0.29/AIN5_P$A10") (pintype "bidirectional"))
    )
    (net (code "67") (name "P0.30") (class "Default")
      (node (ref "U1") (pin "P$B9") (pinfunction "P0.30/AIN6_P$B9") (pintype "bidirectional"))
    )
    (net (code "68") (name "P0.31") (class "Default")
      (node (ref "U1") (pin "P$A8") (pinfunction "P0.31/AIN7_P$A8") (pintype "bidirectional"))
    )
    (net (code "69") (name "P1.01") (class "Default")
      (node (ref "Q1") (pin "1") (pinfunction "G_1") (pintype "bidirectional"))
      (node (ref "R_PWR_EPD") (pin "1") (pinfunction "1_1") (pintype "bidirectional"))
      (node (ref "U1") (pin "P$Y23") (pinfunction "P1.01_P$Y23") (pintype "bidirectional"))
    )
    (net (code "70") (name "P1.02") (class "Default")
      (node (ref "C29") (pin "1") (pinfunction "1_1") (pintype "passive"))
      (node (ref "R7") (pin "1") (pinfunction "1_1") (pintype "bidirectional"))
      (node (ref "SW_DN") (pin "2") (pinfunction "2_2") (pintype "passive"))
      (node (ref "U1") (pin "P$W24") (pinfunction "P1.02_P$W24") (pintype "bidirectional"))
    )
    (net (code "71") (name "P1.03") (class "Default")
      (node (ref "U1") (pin "P$V23") (pinfunction "P1.03_P$V23") (pintype "bidirectional"))
    )
    (net (code "72") (name "P1.04") (class "Default")
      (node (ref "U1") (pin "P$U24") (pinfunction "P1.04_P$U24") (pintype "bidirectional"))
    )
    (net (code "73") (name "P1.05") (class "Default")
      (node (ref "U1") (pin "P$T23") (pinfunction "P1.05_P$T23") (pintype "bidirectional"))
    )
    (net (code "74") (name "P1.06") (class "Default")
      (node (ref "U1") (pin "P$R24") (pinfunction "P1.06_P$R24") (pintype "bidirectional"))
    )
    (net (code "75") (name "P1.07") (class "Default")
      (node (ref "U1") (pin "P$P23") (pinfunction "P1.07_P$P23") (pintype "bidirectional"))
    )
    (net (code "76") (name "P1.09") (class "Default")
      (node (ref "U1") (pin "P$R1") (pinfunction "P1.09_P$R1") (pintype "bidirectional"))
    )
    (net (code "77") (name "P1.10") (class "Default")
      (node (ref "U1") (pin "P$A20") (pinfunction "P1.10_P$A20") (pintype "bidirectional"))
    )
    (net (code "78") (name "P1.11") (class "Default")
      (node (ref "U1") (pin "P$B19") (pinfunction "P1.11_P$B19") (pintype "bidirectional"))
    )
    (net (code "79") (name "P1.12") (class "Default")
      (node (ref "U1") (pin "P$B17") (pinfunction "P1.12_P$B17") (pintype "bidirectional"))
    )
    (net (code "80") (name "P1.13") (class "Default")
      (node (ref "U1") (pin "P$A16") (pinfunction "P1.13_P$A16") (pintype "bidirectional"))
    )
    (net (code "81") (name "P1.14") (class "Default")
      (node (ref "U1") (pin "P$B15") (pinfunction "P1.14_P$B15") (pintype "bidirectional"))
    )
    (net (code "82") (name "P1.15") (class "Default")
      (node (ref "U1") (pin "P$A14") (pinfunction "P1.15_P$A14") (pintype "bidirectional"))
    )
    (net (code "83") (name "PMIC_INT") (class "Default")
      (node (ref "IC1") (pin "A1") (pinfunction "~{INT}_A1") (pintype "bidirectional"))
      (node (ref "U1") (pin "P$T2") (pinfunction "P0.11_P$T2") (pintype "bidirectional"))
    )
    (net (code "84") (name "PREVGH") (class "Default")
      (node (ref "D5") (pin "1") (pinfunction "K_1") (pintype "bidirectional"))
      (node (ref "EPD_C9") (pin "2") (pinfunction "2_2") (pintype "passive"))
      (node (ref "J1") (pin "21") (pinfunction "21_21") (pintype "bidirectional"))
    )
    (net (code "85") (name "PREVGL") (class "Default")
      (node (ref "D2") (pin "2") (pinfunction "A_2") (pintype "bidirectional"))
      (node (ref "EPD_C11") (pin "2") (pinfunction "2_2") (pintype "passive"))
      (node (ref "J1") (pin "23") (pinfunction "23_23") (pintype "bidirectional"))
    )
    (net (code "86") (name "RESE") (class "Default")
      (node (ref "J1") (pin "3") (pinfunction "3_3") (pintype "bidirectional"))
      (node (ref "Q3") (pin "2") (pinfunction "S_2") (pintype "bidirectional"))
      (node (ref "R1_EP_DR") (pin "2") (pinfunction "2_2") (pintype "bidirectional"))
    )
    (net (code "87") (name "RESET") (class "Default")
      (node (ref "J2") (pin "6") (pinfunction "6_6") (pintype "bidirectional"))
      (node (ref "TP_RESET") (pin "TP") (pinfunction "TP_TP") (pintype "input"))
      (node (ref "U1") (pin "P$AC13") (pinfunction "P0.18/RESET_P$AC13") (pintype "bidirectional"))
    )
    (net (code "88") (name "RF") (class "Default")
      (node (ref "ANT1") (pin "1") (pinfunction "FEED_1") (pintype "input"))
      (node (ref "C22") (pin "2") (pinfunction "2_2") (pintype "passive"))
      (node (ref "C4") (pin "2") (pinfunction "2_2") (pintype "passive"))
      (node (ref "L1") (pin "1") (pinfunction "1_1") (pintype "passive"))
    )
    (net (code "89") (name "SCK") (class "Default")
      (node (ref "J1") (pin "13") (pinfunction "13_13") (pintype "bidirectional"))
      (node (ref "U1") (pin "P$A12") (pinfunction "P0.02/AIN0_P$A12") (pintype "bidirectional"))
    )
    (net (code "90") (name "SCL") (class "Default")
      (node (ref "IC1") (pin "B1") (pinfunction "SCL_B1") (pintype "bidirectional"))
      (node (ref "IC2") (pin "C1") (pinfunction "SCL_C1") (pintype "bidirectional"))
      (node (ref "IC3") (pin "12") (pinfunction "SCX_12") (pintype "bidirectional"))
      (node (ref "R17") (pin "2") (pinfunction "2_2") (pintype "bidirectional"))
      (node (ref "R4") (pin "1") (pinfunction "1_1") (pintype "bidirectional"))
      (node (ref "TP_SCL") (pin "TP") (pinfunction "TP_TP") (pintype "input"))
      (node (ref "U1") (pin "P$M2") (pinfunction "P0.07_P$M2") (pintype "bidirectional"))
      (node (ref "U3") (pin "7") (pinfunction "SCL_7") (pintype "input"))
    )
    (net (code "91") (name "SDA") (class "Default")
      (node (ref "IC1") (pin "C1") (pinfunction "SDA_C1") (pintype "bidirectional"))
      (node (ref "IC2") (pin "B2") (pinfunction "SDA_B2") (pintype "bidirectional"))
      (node (ref "IC3") (pin "2") (pinfunction "SDX_2") (pintype "bidirectional"))
      (node (ref "R18") (pin "2") (pinfunction "2_2") (pintype "bidirectional"))
      (node (ref "R2") (pin "1") (pinfunction "1_1") (pintype "bidirectional"))
      (node (ref "TP_SDA") (pin "TP") (pinfunction "TP_TP") (pintype "input"))
      (node (ref "U1") (pin "P$L1") (pinfunction "P0.06_P$L1") (pintype "bidirectional"))
      (node (ref "U3") (pin "8") (pinfunction "SDA_8") (pintype "bidirectional"))
    )
    (net (code "92") (name "SWDCLK") (class "Default")
      (node (ref "J2") (pin "4") (pinfunction "4_4") (pintype "bidirectional"))
      (node (ref "TP_SWDCLK") (pin "TP") (pinfunction "TP_TP") (pintype "input"))
      (node (ref "U1") (pin "P$AA24") (pinfunction "SWDCLK_P$AA24") (pintype "input"))
    )
    (net (code "93") (name "SWDIO") (class "Default")
      (node (ref "J2") (pin "2") (pinfunction "2_2") (pintype "bidirectional"))
      (node (ref "TP_SWDIO") (pin "TP") (pinfunction "TP_TP") (pintype "input"))
      (node (ref "U1") (pin "P$AC24") (pinfunction "SWDIO_P$AC24") (pintype "bidirectional"))
    )
    (net (code "94") (name "SWO") (class "Default")
      (node (ref "TP_SWO") (pin "TP") (pinfunction "TP_TP") (pintype "input"))
      (node (ref "U1") (pin "P$AD22") (pinfunction "P1.00_P$AD22") (pintype "bidirectional"))
    )
    (net (code "95") (name "VBAT") (class "Default")
      (node (ref "C27") (pin "2") (pinfunction "2_2") (pintype "passive"))
      (node (ref "C37") (pin "2") (pinfunction "2_2") (pintype "passive"))
      (node (ref "IC1") (pin "C2") (pinfunction "BAT_C2") (pintype "bidirectional"))
      (node (ref "TP_VBAT") (pin "TP") (pinfunction "TP_TP") (pintype "input"))
      (node (ref "U3") (pin "2") (pinfunction "CELL_2") (pintype "power_in"))
      (node (ref "U3") (pin "3") (pinfunction "VDD_3") (pintype "power_in"))
    )
    (net (code "96") (name "VBUS") (class "Default")
      (node (ref "C21") (pin "2") (pinfunction "2_2") (pintype "passive"))
      (node (ref "C38") (pin "2") (pinfunction "2_2") (pintype "passive"))
      (node (ref "C42") (pin "1") (pinfunction "1_1") (pintype "passive"))
      (node (ref "C43") (pin "2") (pinfunction "2_2") (pintype "passive"))
      (node (ref "D3") (pin "5") (pinfunction "VBUS_5") (pintype "bidirectional"))
      (node (ref "IC1") (pin "A2") (pinfunction "IN_A2") (pintype "bidirectional"))
      (node (ref "J4") (pin "A4_B9") (pinfunction "VBUS_A4_B9") (pintype "power_in"))
      (node (ref "J4") (pin "A9_B4") (pinfunction "VBUS_A9_B4") (pintype "power_in"))
      (node (ref "U1") (pin "P$AD2") (pinfunction "VBUS_P$AD2") (pintype "power_in"))
    )
    (net (code "97") (name "VREG") (class "Default")
      (node (ref "C23") (pin "1") (pinfunction "1_1") (pintype "passive"))
      (node (ref "C24") (pin "2") (pinfunction "2_2") (pintype "passive"))
      (node (ref "C39") (pin "1") (pinfunction "1_1") (pintype "passive"))
      (node (ref "IC1") (pin "B2") (pinfunction "SYS_B2") (pintype "bidirectional"))
      (node (ref "IC9") (pin "A1") (pinfunction "EN_A1") (pintype "bidirectional"))
      (node (ref "IC9") (pin "A2") (pinfunction "VIN_1_A2") (pintype "bidirectional"))
      (node (ref "IC9") (pin "A3") (pinfunction "VIN_2_A3") (pintype "bidirectional"))
      (node (ref "TP_VREG") (pin "TP") (pinfunction "TP_TP") (pintype "input"))
    )
    (net (code "98") (name "unconnected-(ANT1-NC-Pad2)") (class "Default")
      (node (ref "ANT1") (pin "2") (pinfunction "NC_2") (pintype "no_connect"))
    )
    (net (code "99") (name "unconnected-(IC3-ASCL-Pad11)") (class "Default")
      (node (ref "IC3") (pin "11") (pinfunction "ASCL_11") (pintype "bidirectional"))
    )
    (net (code "100") (name "unconnected-(IC3-ASDA-Pad4)") (class "Default")
      (node (ref "IC3") (pin "4") (pinfunction "ASDA_4") (pintype "bidirectional"))
    )
    (net (code "101") (name "unconnected-(IC9-SW1_2-PadB3)") (class "Default")
      (node (ref "IC9") (pin "B3") (pinfunction "SW1_2_B3") (pintype "bidirectional"))
    )
    (net (code "102") (name "unconnected-(J1-Pad1)") (class "Default")
      (node (ref "J1") (pin "1") (pinfunction "1_1") (pintype "bidirectional"))
    )
    (net (code "103") (name "unconnected-(J1-Pad6)") (class "Default")
      (node (ref "J1") (pin "6") (pinfunction "6_6") (pintype "bidirectional"))
    )
    (net (code "104") (name "unconnected-(J1-Pad7)") (class "Default")
      (node (ref "J1") (pin "7") (pinfunction "7_7") (pintype "bidirectional"))
    )
    (net (code "105") (name "unconnected-(J4-SBU1-PadA8)") (class "Default")
      (node (ref "J4") (pin "A8") (pinfunction "SBU1_A8") (pintype "bidirectional"))
    )
    (net (code "106") (name "unconnected-(J4-SBU2-PadB8)") (class "Default")
      (node (ref "J4") (pin "B8") (pinfunction "SBU2_B8") (pintype "bidirectional"))
    )
    (net (code "107") (name "unconnected-(U1-DCCH-PadP$AB2)") (class "Default")
      (node (ref "U1") (pin "P$AB2") (pinfunction "DCCH_P$AB2") (pintype "bidirectional"))
    )
  )
)
